# Drone_Powerv2_0.net
KiCad netlist of a schematic drawn in Altium Designer
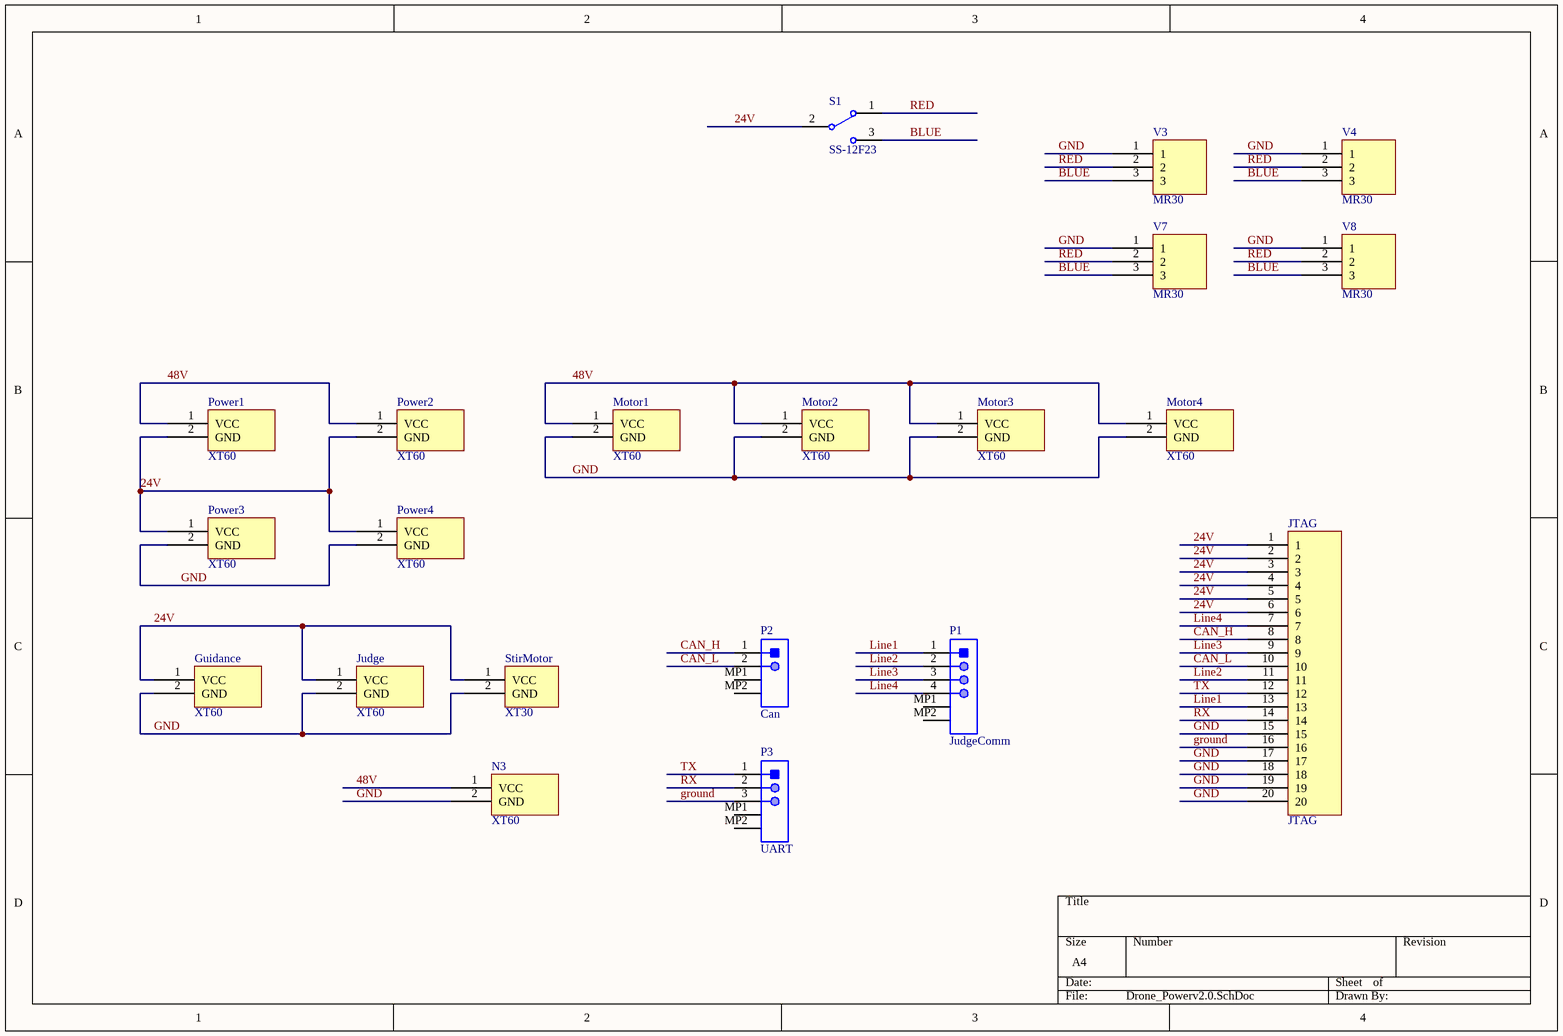
[diagram p0: Drone_Powerv2.0.SchDoc]

(export (version "E")
  (design (tool "Eeschema 10.0.6"))
  (components
    (comp (ref "Guidance")
      (value "XT60")
      (footprint "TX60UPB-F")
      (libsource (lib "Amass电源插头") (part "XT60电源插头"))
    )
    (comp (ref "JTAG") (value "JTAG") (footprint "JTAG:IDC20S") (libsource (lib "JTAG") (part "JTAG")))
    (comp (ref "Judge")
      (value "XT60")
      (footprint "TX60UPB-F")
      (libsource (lib "Amass电源插头") (part "XT60电源插头"))
    )
    (comp (ref "Motor1")
      (value "XT60")
      (footprint "TX60UPB-F")
      (libsource (lib "Amass电源插头") (part "XT60电源插头"))
    )
    (comp (ref "Motor2")
      (value "XT60")
      (footprint "TX60UPB-F")
      (libsource (lib "Amass电源插头") (part "XT60电源插头"))
    )
    (comp (ref "Motor3")
      (value "XT60")
      (footprint "TX60UPB-F")
      (libsource (lib "Amass电源插头") (part "XT60电源插头"))
    )
    (comp (ref "Motor4")
      (value "XT60")
      (footprint "TX60UPB-F")
      (libsource (lib "Amass电源插头") (part "XT60电源插头"))
    )
    (comp (ref "N3") (value "XT60") (footprint "TX60UPB-F") (libsource (lib "Amass电源插头") (part "XT60电源插头")))
    (comp (ref "P1")
      (value "JudgeComm")
      (footprint "JST GH connector:JST-BM04B-GHS-TBT_V")
      (fields (field (name "MANUFACTURER") "JST"))
      (libsource (lib "JST GH connector") (part "BM04B-GHS-TBT(LF)(SN)"))
    )
    (comp (ref "P2")
      (value "Can")
      (footprint "JST-SM02B-GHS-TB_V")
      (fields (field (name "MANUFACTURER") "JST"))
      (libsource (lib "JST GH connector") (part "SM02B-GHS-TB(LF)(SN)"))
    )
    (comp (ref "P3")
      (value "UART")
      (footprint "JST-BM03B-GHS-TBT_V")
      (fields (field (name "MANUFACTURER") "JST"))
      (libsource (lib "JST GH connector") (part "BM03B-GHS-TBT(LF)(SN)"))
    )
    (comp (ref "Power1")
      (value "XT60")
      (footprint "TX60UPB-F")
      (libsource (lib "Amass电源插头") (part "XT60电源插头"))
    )
    (comp (ref "Power2")
      (value "XT60")
      (footprint "TX60UPB-F")
      (libsource (lib "Amass电源插头") (part "XT60电源插头"))
    )
    (comp (ref "Power3")
      (value "XT60")
      (footprint "TX60PW-F20")
      (libsource (lib "Amass电源插头") (part "XT60电源插头"))
    )
    (comp (ref "Power4")
      (value "XT60")
      (footprint "TX60PW-F20")
      (libsource (lib "Amass电源插头") (part "XT60电源插头"))
    )
    (comp (ref "S1")
      (value "SS-12F23")
      (footprint "SK-12D07VG3")
      (description "1路波动开关")
      (libsource (lib "5.1   - 按键-开关") (part "SSW-1P"))
    )
    (comp (ref "StirMotor")
      (value "XT30")
      (footprint "XT30PW-F30")
      (libsource (lib "Amass电源插头") (part "XT30电源插头"))
    )
    (comp (ref "V3") (value "MR30") (footprint "MR30PB-F") (libsource (lib "Amass电源插头") (part "MR电源插头")))
    (comp (ref "V4") (value "MR30") (footprint "MR30PB-F") (libsource (lib "Amass电源插头") (part "MR电源插头")))
    (comp (ref "V7") (value "MR30") (footprint "MR30PB-F") (libsource (lib "Amass电源插头") (part "MR电源插头")))
    (comp (ref "V8") (value "MR30") (footprint "MR30PB-F") (libsource (lib "Amass电源插头") (part "MR电源插头")))
  )
  (nets
    (net (code "1") (name "/24V") (class "Default")
      (node (ref "Guidance") (pin "1") (pinfunction "VCC_1") (pintype "passive"))
      (node (ref "JTAG") (pin "1") (pinfunction "1_1") (pintype "passive"))
      (node (ref "JTAG") (pin "2") (pinfunction "2_2") (pintype "passive"))
      (node (ref "JTAG") (pin "3") (pinfunction "3_3") (pintype "passive"))
      (node (ref "JTAG") (pin "4") (pinfunction "4_4") (pintype "passive"))
      (node (ref "JTAG") (pin "5") (pinfunction "5_5") (pintype "passive"))
      (node (ref "JTAG") (pin "6") (pinfunction "6_6") (pintype "passive"))
      (node (ref "Judge") (pin "1") (pinfunction "VCC_1") (pintype "passive"))
      (node (ref "Power1") (pin "2") (pinfunction "GND_2") (pintype "passive"))
      (node (ref "Power2") (pin "2") (pinfunction "GND_2") (pintype "passive"))
      (node (ref "Power3") (pin "1") (pinfunction "VCC_1") (pintype "passive"))
      (node (ref "Power4") (pin "1") (pinfunction "VCC_1") (pintype "passive"))
      (node (ref "S1") (pin "2") (pinfunction "2_2") (pintype "passive"))
      (node (ref "StirMotor") (pin "1") (pinfunction "VCC_1") (pintype "power_in"))
    )
    (net (code "2") (name "/48V") (class "Default")
      (node (ref "Motor1") (pin "1") (pinfunction "VCC_1") (pintype "passive"))
      (node (ref "Motor2") (pin "1") (pinfunction "VCC_1") (pintype "passive"))
      (node (ref "Motor3") (pin "1") (pinfunction "VCC_1") (pintype "passive"))
      (node (ref "Motor4") (pin "1") (pinfunction "VCC_1") (pintype "passive"))
      (node (ref "N3") (pin "1") (pinfunction "VCC_1") (pintype "passive"))
      (node (ref "Power1") (pin "1") (pinfunction "VCC_1") (pintype "passive"))
      (node (ref "Power2") (pin "1") (pinfunction "VCC_1") (pintype "passive"))
    )
    (net (code "3") (name "/BLUE") (class "Default")
      (node (ref "S1") (pin "3") (pinfunction "3_3") (pintype "passive"))
      (node (ref "V3") (pin "3") (pinfunction "3_3") (pintype "power_in"))
      (node (ref "V4") (pin "3") (pinfunction "3_3") (pintype "power_in"))
      (node (ref "V7") (pin "3") (pinfunction "3_3") (pintype "power_in"))
      (node (ref "V8") (pin "3") (pinfunction "3_3") (pintype "power_in"))
    )
    (net (code "4") (name "/CAN_H") (class "Default")
      (node (ref "JTAG") (pin "8") (pinfunction "8_8") (pintype "passive"))
      (node (ref "P2") (pin "1") (pinfunction "1_1") (pintype "passive"))
    )
    (net (code "5") (name "/CAN_L") (class "Default")
      (node (ref "JTAG") (pin "10") (pinfunction "10_10") (pintype "passive"))
      (node (ref "P2") (pin "2") (pinfunction "2_2") (pintype "passive"))
    )
    (net (code "6") (name "/GND") (class "Default")
      (node (ref "Guidance") (pin "2") (pinfunction "GND_2") (pintype "passive"))
      (node (ref "JTAG") (pin "15") (pinfunction "15_15") (pintype "passive"))
      (node (ref "JTAG") (pin "17") (pinfunction "17_17") (pintype "passive"))
      (node (ref "JTAG") (pin "18") (pinfunction "18_18") (pintype "passive"))
      (node (ref "JTAG") (pin "19") (pinfunction "19_19") (pintype "passive"))
      (node (ref "JTAG") (pin "20") (pinfunction "20_20") (pintype "passive"))
      (node (ref "Judge") (pin "2") (pinfunction "GND_2") (pintype "passive"))
      (node (ref "Motor1") (pin "2") (pinfunction "GND_2") (pintype "passive"))
      (node (ref "Motor2") (pin "2") (pinfunction "GND_2") (pintype "passive"))
      (node (ref "Motor3") (pin "2") (pinfunction "GND_2") (pintype "passive"))
      (node (ref "Motor4") (pin "2") (pinfunction "GND_2") (pintype "passive"))
      (node (ref "N3") (pin "2") (pinfunction "GND_2") (pintype "passive"))
      (node (ref "Power3") (pin "2") (pinfunction "GND_2") (pintype "passive"))
      (node (ref "Power4") (pin "2") (pinfunction "GND_2") (pintype "passive"))
      (node (ref "StirMotor") (pin "2") (pinfunction "GND_2") (pintype "power_in"))
      (node (ref "V3") (pin "1") (pinfunction "1_1") (pintype "power_in"))
      (node (ref "V4") (pin "1") (pinfunction "1_1") (pintype "power_in"))
      (node (ref "V7") (pin "1") (pinfunction "1_1") (pintype "power_in"))
      (node (ref "V8") (pin "1") (pinfunction "1_1") (pintype "power_in"))
    )
    (net (code "7") (name "/Line1") (class "Default")
      (node (ref "JTAG") (pin "13") (pinfunction "13_13") (pintype "passive"))
      (node (ref "P1") (pin "1") (pinfunction "1_1") (pintype "passive"))
    )
    (net (code "8") (name "/Line2") (class "Default")
      (node (ref "JTAG") (pin "11") (pinfunction "11_11") (pintype "passive"))
      (node (ref "P1") (pin "2") (pinfunction "2_2") (pintype "passive"))
    )
    (net (code "9") (name "/Line3") (class "Default")
      (node (ref "JTAG") (pin "9") (pinfunction "9_9") (pintype "passive"))
      (node (ref "P1") (pin "3") (pinfunction "3_3") (pintype "passive"))
    )
    (net (code "10") (name "/Line4") (class "Default")
      (node (ref "JTAG") (pin "7") (pinfunction "7_7") (pintype "passive"))
      (node (ref "P1") (pin "4") (pinfunction "4_4") (pintype "passive"))
    )
    (net (code "11") (name "/RED") (class "Default")
      (node (ref "S1") (pin "1") (pinfunction "1_1") (pintype "passive"))
      (node (ref "V3") (pin "2") (pinfunction "2_2") (pintype "power_in"))
      (node (ref "V4") (pin "2") (pinfunction "2_2") (pintype "power_in"))
      (node (ref "V7") (pin "2") (pinfunction "2_2") (pintype "power_in"))
      (node (ref "V8") (pin "2") (pinfunction "2_2") (pintype "power_in"))
    )
    (net (code "12") (name "/RX") (class "Default")
      (node (ref "JTAG") (pin "14") (pinfunction "14_14") (pintype "passive"))
      (node (ref "P3") (pin "2") (pinfunction "2_2") (pintype "passive"))
    )
    (net (code "13") (name "/TX") (class "Default")
      (node (ref "JTAG") (pin "12") (pinfunction "12_12") (pintype "passive"))
      (node (ref "P3") (pin "1") (pinfunction "1_1") (pintype "passive"))
    )
    (net (code "14") (name "/ground") (class "Default")
      (node (ref "JTAG") (pin "16") (pinfunction "16_16") (pintype "passive"))
      (node (ref "P3") (pin "3") (pinfunction "3_3") (pintype "passive"))
    )
    (net (code "15") (name "unconnected-(P1-PadMP1)") (class "Default")
      (node (ref "P1") (pin "MP1") (pinfunction "MP1_MP1") (pintype "passive"))
    )
    (net (code "16") (name "unconnected-(P1-PadMP2)") (class "Default")
      (node (ref "P1") (pin "MP2") (pinfunction "MP2_MP2") (pintype "passive"))
    )
    (net (code "17") (name "unconnected-(P2-PadMP1)") (class "Default")
      (node (ref "P2") (pin "MP1") (pinfunction "MP1_MP1") (pintype "passive"))
    )
    (net (code "18") (name "unconnected-(P2-PadMP2)") (class "Default")
      (node (ref "P2") (pin "MP2") (pinfunction "MP2_MP2") (pintype "passive"))
    )
    (net (code "19") (name "unconnected-(P3-PadMP1)") (class "Default")
      (node (ref "P3") (pin "MP1") (pinfunction "MP1_MP1") (pintype "passive"))
    )
    (net (code "20") (name "unconnected-(P3-PadMP2)") (class "Default")
      (node (ref "P3") (pin "MP2") (pinfunction "MP2_MP2") (pintype "passive"))
    )
  )
)
